# PCB_mini.net
KiCad netlist of a schematic drawn in Altium Designer
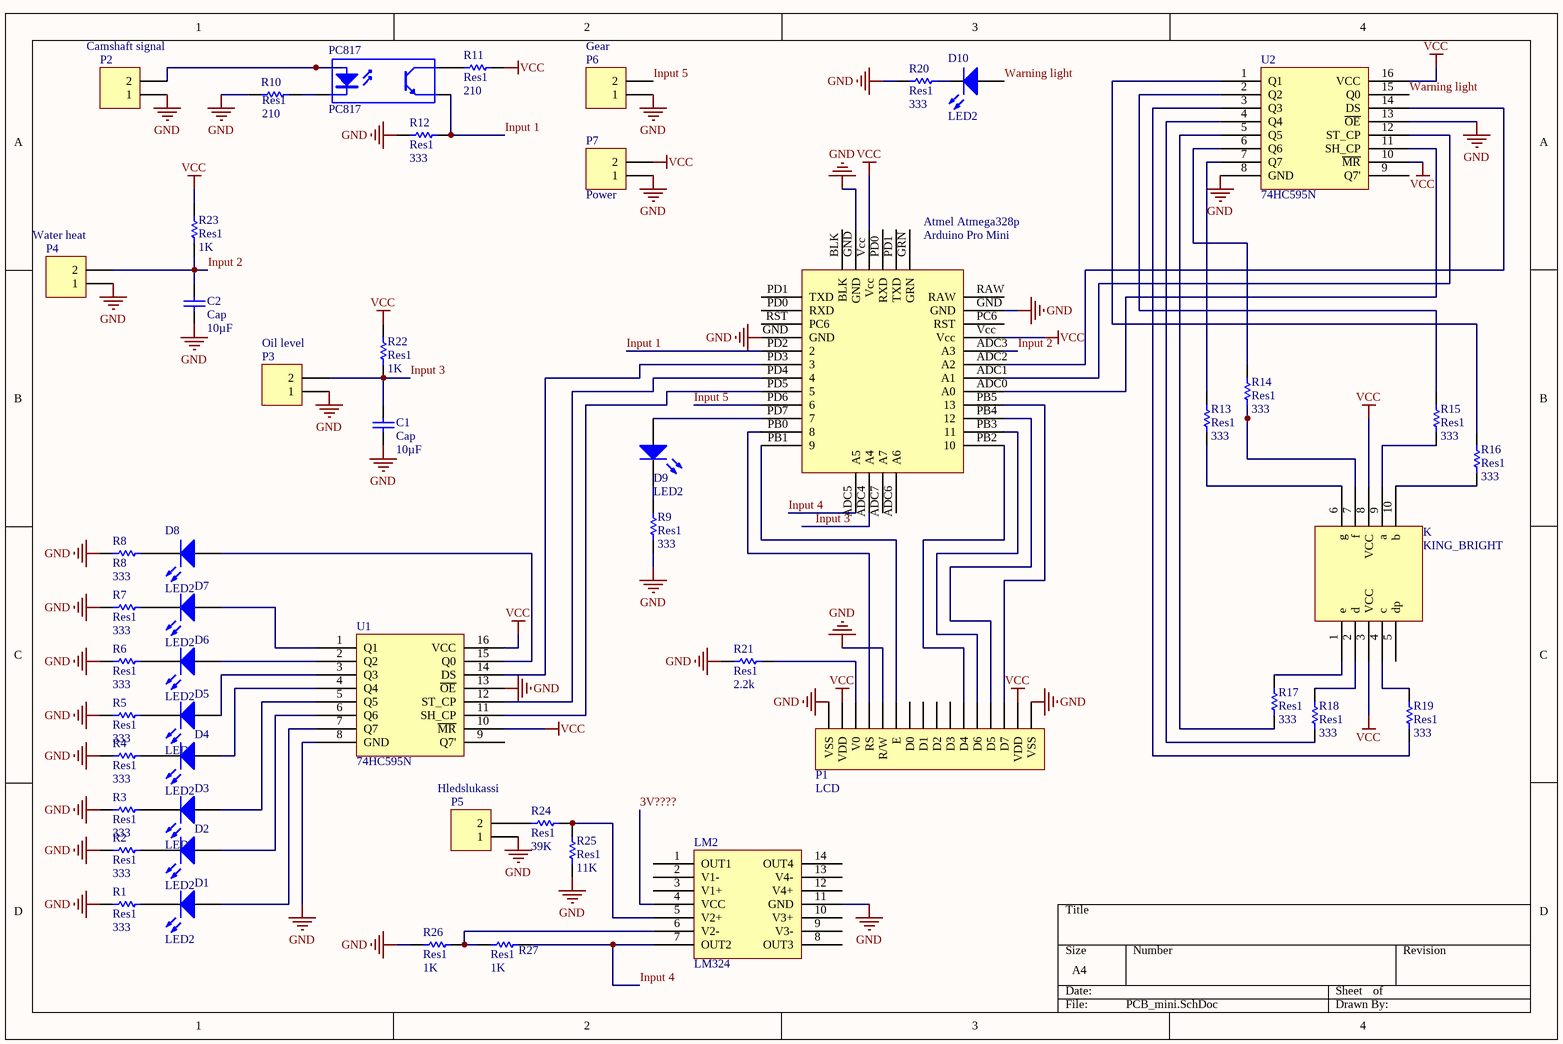
[diagram p0: PCB_mini.SchDoc]

(export (version "E")
  (design (tool "Eeschema 10.0.6"))
  (components
    (comp (ref "Arduino Pro Mini")
      (value "Atmel Atmega328p")
      (footprint "ArduinoProMini")
      (libsource (lib "ArduinoNano") (part "ArduinoProMini"))
    )
    (comp (ref "C1")
      (value "Cap")
      (footprint "1206 footprint")
      (fields (field (name "ALTIUM_VALUE") "10µF"))
      (libsource (lib "ArduinoNano (1)") (part "Cap"))
    )
    (comp (ref "C2")
      (value "Cap")
      (footprint "1206 footprint")
      (fields (field (name "ALTIUM_VALUE") "10µF"))
      (libsource (lib "ArduinoNano (1)") (part "Cap"))
    )
    (comp (ref "D1")
      (value "LED2")
      (footprint "3.2X1.6X1.1")
      (description "Typical RED, GREEN, YELLOW, AMBER GaAs LED")
      (fields (field (name "PUBLISHER") "Altium Limited"))
      (libsource (lib "Miscellaneous Devices") (part "LED2"))
    )
    (comp (ref "D2")
      (value "LED2")
      (footprint "3.2X1.6X1.1")
      (description "Typical RED, GREEN, YELLOW, AMBER GaAs LED")
      (fields (field (name "PUBLISHER") "Altium Limited"))
      (libsource (lib "Miscellaneous Devices") (part "LED2"))
    )
    (comp (ref "D3")
      (value "LED2")
      (footprint "3.2X1.6X1.1")
      (description "Typical RED, GREEN, YELLOW, AMBER GaAs LED")
      (fields (field (name "PUBLISHER") "Altium Limited"))
      (libsource (lib "Miscellaneous Devices") (part "LED2"))
    )
    (comp (ref "D4")
      (value "LED2")
      (footprint "3.2X1.6X1.1")
      (description "Typical RED, GREEN, YELLOW, AMBER GaAs LED")
      (fields (field (name "PUBLISHER") "Altium Limited"))
      (libsource (lib "Miscellaneous Devices") (part "LED2"))
    )
    (comp (ref "D5")
      (value "LED2")
      (footprint "3.2X1.6X1.1")
      (description "Typical RED, GREEN, YELLOW, AMBER GaAs LED")
      (fields (field (name "PUBLISHER") "Altium Limited"))
      (libsource (lib "Miscellaneous Devices") (part "LED2"))
    )
    (comp (ref "D6")
      (value "LED2")
      (footprint "3.2X1.6X1.1")
      (description "Typical RED, GREEN, YELLOW, AMBER GaAs LED")
      (fields (field (name "PUBLISHER") "Altium Limited"))
      (libsource (lib "Miscellaneous Devices") (part "LED2"))
    )
    (comp (ref "D7")
      (value "LED2")
      (footprint "3.2X1.6X1.1")
      (description "Typical RED, GREEN, YELLOW, AMBER GaAs LED")
      (fields (field (name "PUBLISHER") "Altium Limited"))
      (libsource (lib "Miscellaneous Devices") (part "LED2"))
    )
    (comp (ref "D8")
      (value "LED2")
      (footprint "3.2X1.6X1.1")
      (description "Typical RED, GREEN, YELLOW, AMBER GaAs LED")
      (fields (field (name "PUBLISHER") "Altium Limited"))
      (libsource (lib "Miscellaneous Devices") (part "LED2"))
    )
    (comp (ref "D9")
      (value "LED2")
      (footprint "3.2X1.6X1.1")
      (description "Typical RED, GREEN, YELLOW, AMBER GaAs LED")
      (fields (field (name "PUBLISHER") "Altium Limited"))
      (libsource (lib "Miscellaneous Devices") (part "LED2"))
    )
    (comp (ref "D10")
      (value "LED2")
      (footprint "3.2X1.6X1.1")
      (description "Typical RED, GREEN, YELLOW, AMBER GaAs LED")
      (fields (field (name "PUBLISHER") "Altium Limited"))
      (libsource (lib "Miscellaneous Devices") (part "LED2"))
    )
    (comp (ref "K")
      (value "KING_BRIGHT")
      (footprint "KNIGHT_BRIGHT")
      (libsource (lib "ArduinoNano") (part "KING_BRIGHT"))
    )
    (comp (ref "LM2") (value "LM324") (footprint "SOP-14") (libsource (lib "ArduinoNano") (part "LM324")))
    (comp (ref "P1")
      (value "LCD")
      (footprint "HDR1X16")
      (description "Header, 16-Pin")
      (fields (field (name "PUBLISHER") "Altium Limited"))
      (libsource (lib "Miscellaneous Connectors") (part "Header 16"))
    )
    (comp (ref "P2")
      (value "Camshaft signal")
      (footprint "HDR1X2")
      (description "Header, 2-Pin")
      (fields (field (name "PUBLISHER") "Altium Limited"))
      (libsource (lib "Miscellaneous Connectors") (part "Header 2"))
    )
    (comp (ref "P3")
      (value "Oil level")
      (footprint "HDR1X2")
      (description "Header, 2-Pin")
      (fields (field (name "PUBLISHER") "Altium Limited"))
      (libsource (lib "Miscellaneous Connectors") (part "Header 2"))
    )
    (comp (ref "P4")
      (value "Water heat")
      (footprint "HDR1X2")
      (description "Header, 2-Pin")
      (fields (field (name "PUBLISHER") "Altium Limited"))
      (libsource (lib "Miscellaneous Connectors") (part "Header 2"))
    )
    (comp (ref "P5")
      (value "Hledslukassi")
      (footprint "HDR1X2")
      (description "Header, 2-Pin")
      (fields (field (name "PUBLISHER") "Altium Limited"))
      (libsource (lib "Miscellaneous Connectors") (part "Header 2"))
    )
    (comp (ref "P6")
      (value "Gear")
      (footprint "HDR1X2")
      (description "Header, 2-Pin")
      (fields (field (name "PUBLISHER") "Altium Limited"))
      (libsource (lib "Miscellaneous Connectors") (part "Header 2"))
    )
    (comp (ref "P7")
      (value "Power")
      (footprint "HDR1X2")
      (description "Header, 2-Pin")
      (fields (field (name "PUBLISHER") "Altium Limited"))
      (libsource (lib "Miscellaneous Connectors") (part "Header 2"))
    )
    (comp (ref "PC817")
      (value "PC817")
      (footprint "PC817 SMT")
      (libsource (lib "ArduinoNano") (part "PC817"))
    )
    (comp (ref "R1")
      (value "Res1")
      (footprint "AXIAL-0.3")
      (description "Resistor")
      (fields (field (name "ALTIUM_VALUE") "333") (field (name "PUBLISHER") "Altium Limited"))
      (libsource (lib "Miscellaneous Devices") (part "Res1"))
    )
    (comp (ref "R2")
      (value "Res1")
      (footprint "AXIAL-0.3")
      (description "Resistor")
      (fields (field (name "ALTIUM_VALUE") "333") (field (name "PUBLISHER") "Altium Limited"))
      (libsource (lib "Miscellaneous Devices") (part "Res1"))
    )
    (comp (ref "R3")
      (value "Res1")
      (footprint "AXIAL-0.3")
      (description "Resistor")
      (fields (field (name "ALTIUM_VALUE") "333") (field (name "PUBLISHER") "Altium Limited"))
      (libsource (lib "Miscellaneous Devices") (part "Res1"))
    )
    (comp (ref "R4")
      (value "Res1")
      (footprint "AXIAL-0.3")
      (description "Resistor")
      (fields (field (name "ALTIUM_VALUE") "333") (field (name "PUBLISHER") "Altium Limited"))
      (libsource (lib "Miscellaneous Devices") (part "Res1"))
    )
    (comp (ref "R5")
      (value "Res1")
      (footprint "AXIAL-0.3")
      (description "Resistor")
      (fields (field (name "ALTIUM_VALUE") "333") (field (name "PUBLISHER") "Altium Limited"))
      (libsource (lib "Miscellaneous Devices") (part "Res1"))
    )
    (comp (ref "R6")
      (value "Res1")
      (footprint "AXIAL-0.3")
      (description "Resistor")
      (fields (field (name "ALTIUM_VALUE") "333") (field (name "PUBLISHER") "Altium Limited"))
      (libsource (lib "Miscellaneous Devices") (part "Res1"))
    )
    (comp (ref "R7")
      (value "Res1")
      (footprint "AXIAL-0.3")
      (description "Resistor")
      (fields (field (name "ALTIUM_VALUE") "333") (field (name "PUBLISHER") "Altium Limited"))
      (libsource (lib "Miscellaneous Devices") (part "Res1"))
    )
    (comp (ref "R8")
      (value "R8")
      (footprint "AXIAL-0.3")
      (description "Resistor")
      (fields (field (name "ALTIUM_VALUE") "333") (field (name "PUBLISHER") "Altium Limited"))
      (libsource (lib "Miscellaneous Devices") (part "Res1"))
    )
    (comp (ref "R9")
      (value "Res1")
      (footprint "AXIAL-0.3")
      (description "Resistor")
      (fields (field (name "ALTIUM_VALUE") "333") (field (name "PUBLISHER") "Altium Limited"))
      (libsource (lib "Miscellaneous Devices") (part "Res1"))
    )
    (comp (ref "R10")
      (value "Res1")
      (footprint "AXIAL-0.3")
      (description "Resistor")
      (fields (field (name "ALTIUM_VALUE") "210") (field (name "PUBLISHER") "Altium Limited"))
      (libsource (lib "Miscellaneous Devices") (part "Res1"))
    )
    (comp (ref "R11")
      (value "Res1")
      (footprint "AXIAL-0.3")
      (description "Resistor")
      (fields (field (name "ALTIUM_VALUE") "210") (field (name "PUBLISHER") "Altium Limited"))
      (libsource (lib "Miscellaneous Devices") (part "Res1"))
    )
    (comp (ref "R12")
      (value "Res1")
      (footprint "AXIAL-0.3")
      (description "Resistor")
      (fields (field (name "ALTIUM_VALUE") "333") (field (name "PUBLISHER") "Altium Limited"))
      (libsource (lib "Miscellaneous Devices") (part "Res1"))
    )
    (comp (ref "R13")
      (value "Res1")
      (footprint "AXIAL-0.3")
      (description "Resistor")
      (fields (field (name "ALTIUM_VALUE") "333") (field (name "PUBLISHER") "Altium Limited"))
      (libsource (lib "Miscellaneous Devices") (part "Res1"))
    )
    (comp (ref "R14")
      (value "Res1")
      (footprint "AXIAL-0.3")
      (description "Resistor")
      (fields (field (name "ALTIUM_VALUE") "333") (field (name "PUBLISHER") "Altium Limited"))
      (libsource (lib "Miscellaneous Devices") (part "Res1"))
    )
    (comp (ref "R15")
      (value "Res1")
      (footprint "AXIAL-0.3")
      (description "Resistor")
      (fields (field (name "ALTIUM_VALUE") "333") (field (name "PUBLISHER") "Altium Limited"))
      (libsource (lib "Miscellaneous Devices") (part "Res1"))
    )
    (comp (ref "R16")
      (value "Res1")
      (footprint "AXIAL-0.3")
      (description "Resistor")
      (fields (field (name "ALTIUM_VALUE") "333") (field (name "PUBLISHER") "Altium Limited"))
      (libsource (lib "Miscellaneous Devices") (part "Res1"))
    )
    (comp (ref "R17")
      (value "Res1")
      (footprint "AXIAL-0.3")
      (description "Resistor")
      (fields (field (name "ALTIUM_VALUE") "333") (field (name "PUBLISHER") "Altium Limited"))
      (libsource (lib "Miscellaneous Devices") (part "Res1"))
    )
    (comp (ref "R18")
      (value "Res1")
      (footprint "AXIAL-0.3")
      (description "Resistor")
      (fields (field (name "ALTIUM_VALUE") "333") (field (name "PUBLISHER") "Altium Limited"))
      (libsource (lib "Miscellaneous Devices") (part "Res1"))
    )
    (comp (ref "R19")
      (value "Res1")
      (footprint "AXIAL-0.3")
      (description "Resistor")
      (fields (field (name "ALTIUM_VALUE") "333") (field (name "PUBLISHER") "Altium Limited"))
      (libsource (lib "Miscellaneous Devices") (part "Res1"))
    )
    (comp (ref "R20")
      (value "Res1")
      (footprint "AXIAL-0.3")
      (description "Resistor")
      (fields (field (name "ALTIUM_VALUE") "333") (field (name "PUBLISHER") "Altium Limited"))
      (libsource (lib "Miscellaneous Devices") (part "Res1"))
    )
    (comp (ref "R21")
      (value "Res1")
      (footprint "AXIAL-0.3")
      (description "Resistor")
      (fields (field (name "ALTIUM_VALUE") "2.2k") (field (name "PUBLISHER") "Altium Limited"))
      (libsource (lib "Miscellaneous Devices") (part "Res1"))
    )
    (comp (ref "R22")
      (value "Res1")
      (footprint "AXIAL-0.3")
      (description "Resistor")
      (fields (field (name "ALTIUM_VALUE") "1K") (field (name "PUBLISHER") "Altium Limited"))
      (libsource (lib "Miscellaneous Devices") (part "Res1"))
    )
    (comp (ref "R23")
      (value "Res1")
      (footprint "AXIAL-0.3")
      (description "Resistor")
      (fields (field (name "ALTIUM_VALUE") "1K") (field (name "PUBLISHER") "Altium Limited"))
      (libsource (lib "Miscellaneous Devices") (part "Res1"))
    )
    (comp (ref "R24")
      (value "Res1")
      (footprint "AXIAL-0.3")
      (description "Resistor")
      (fields (field (name "ALTIUM_VALUE") "39K") (field (name "PUBLISHER") "Altium Limited"))
      (libsource (lib "Miscellaneous Devices") (part "Res1"))
    )
    (comp (ref "R25")
      (value "Res1")
      (footprint "AXIAL-0.3")
      (description "Resistor")
      (fields (field (name "ALTIUM_VALUE") "11K") (field (name "PUBLISHER") "Altium Limited"))
      (libsource (lib "Miscellaneous Devices") (part "Res1"))
    )
    (comp (ref "R26")
      (value "Res1")
      (footprint "AXIAL-0.3")
      (description "Resistor")
      (fields (field (name "ALTIUM_VALUE") "1K") (field (name "PUBLISHER") "Altium Limited"))
      (libsource (lib "Miscellaneous Devices") (part "Res1"))
    )
    (comp (ref "R27")
      (value "Res1")
      (footprint "AXIAL-0.3")
      (description "Resistor")
      (fields (field (name "ALTIUM_VALUE") "1K") (field (name "PUBLISHER") "Altium Limited"))
      (libsource (lib "Miscellaneous Devices") (part "Res1"))
    )
    (comp (ref "U1") (value "74HC595N") (footprint "N14A") (libsource (lib "ArduinoNano") (part "SN74LS06N")))
    (comp (ref "U2") (value "74HC595N") (footprint "N14A") (libsource (lib "ArduinoNano") (part "SN74LS06N")))
  )
  (nets
    (net (code "1") (name "/3V????") (class "Default")
      (node (ref "LM2") (pin "4") (pinfunction "VCC_4") (pintype "passive"))
    )
    (net (code "2") (name "/Input 1") (class "Default")
      (node (ref "Arduino Pro Mini") (pin "PD2") (pinfunction "2_PD2") (pintype "passive"))
      (node (ref "PC817") (pin "3") (pinfunction "E_3") (pintype "passive"))
      (node (ref "R12") (pin "1") (pinfunction "1_1") (pintype "passive"))
    )
    (net (code "3") (name "/Input 2") (class "Default")
      (node (ref "Arduino Pro Mini") (pin "ADC3") (pinfunction "A3_ADC3") (pintype "passive"))
      (node (ref "C2") (pin "2") (pinfunction "2_2") (pintype "passive"))
      (node (ref "P4") (pin "2") (pinfunction "2_2") (pintype "passive"))
      (node (ref "R23") (pin "2") (pinfunction "2_2") (pintype "passive"))
    )
    (net (code "4") (name "/Input 3") (class "Default")
      (node (ref "Arduino Pro Mini") (pin "ADC4") (pinfunction "A4_ADC4") (pintype "passive"))
      (node (ref "C1") (pin "2") (pinfunction "2_2") (pintype "passive"))
      (node (ref "P3") (pin "2") (pinfunction "2_2") (pintype "passive"))
      (node (ref "R22") (pin "2") (pinfunction "2_2") (pintype "passive"))
    )
    (net (code "5") (name "/Input 4") (class "Default")
      (node (ref "Arduino Pro Mini") (pin "ADC5") (pinfunction "A5_ADC5") (pintype "passive"))
      (node (ref "LM2") (pin "7") (pinfunction "OUT2_7") (pintype "passive"))
      (node (ref "R27") (pin "2") (pinfunction "2_2") (pintype "passive"))
    )
    (net (code "6") (name "/Input 5") (class "Default")
      (node (ref "Arduino Pro Mini") (pin "PD6") (pinfunction "6_PD6") (pintype "passive"))
      (node (ref "P6") (pin "2") (pinfunction "2_2") (pintype "passive"))
    )
    (net (code "7") (name "/Warning light") (class "Default")
      (node (ref "D10") (pin "1") (pinfunction "A_1") (pintype "passive"))
      (node (ref "U2") (pin "15") (pinfunction "Q0_15") (pintype "passive"))
    )
    (net (code "8") (name "GND") (class "Default")
      (node (ref "Arduino Pro Mini") (pin "GND") (pinfunction "GND_GND") (pintype "passive"))
      (node (ref "C1") (pin "1") (pinfunction "1_1") (pintype "passive"))
      (node (ref "C2") (pin "1") (pinfunction "1_1") (pintype "passive"))
      (node (ref "LM2") (pin "11") (pinfunction "GND_11") (pintype "passive"))
      (node (ref "P1") (pin "1") (pinfunction "VSS_1") (pintype "passive"))
      (node (ref "P1") (pin "16") (pinfunction "VSS_16") (pintype "passive"))
      (node (ref "P1") (pin "5") (pinfunction "R/W_5") (pintype "passive"))
      (node (ref "P2") (pin "1") (pinfunction "1_1") (pintype "passive"))
      (node (ref "P3") (pin "1") (pinfunction "1_1") (pintype "passive"))
      (node (ref "P4") (pin "1") (pinfunction "1_1") (pintype "passive"))
      (node (ref "P5") (pin "1") (pinfunction "1_1") (pintype "passive"))
      (node (ref "P6") (pin "1") (pinfunction "1_1") (pintype "passive"))
      (node (ref "P7") (pin "1") (pinfunction "1_1") (pintype "passive"))
      (node (ref "R1") (pin "2") (pinfunction "2_2") (pintype "passive"))
      (node (ref "R10") (pin "1") (pinfunction "1_1") (pintype "passive"))
      (node (ref "R12") (pin "2") (pinfunction "2_2") (pintype "passive"))
      (node (ref "R2") (pin "2") (pinfunction "2_2") (pintype "passive"))
      (node (ref "R20") (pin "2") (pinfunction "2_2") (pintype "passive"))
      (node (ref "R21") (pin "1") (pinfunction "1_1") (pintype "passive"))
      (node (ref "R25") (pin "2") (pinfunction "2_2") (pintype "passive"))
      (node (ref "R26") (pin "2") (pinfunction "2_2") (pintype "passive"))
      (node (ref "R3") (pin "2") (pinfunction "2_2") (pintype "passive"))
      (node (ref "R4") (pin "2") (pinfunction "2_2") (pintype "passive"))
      (node (ref "R5") (pin "2") (pinfunction "2_2") (pintype "passive"))
      (node (ref "R6") (pin "2") (pinfunction "2_2") (pintype "passive"))
      (node (ref "R7") (pin "2") (pinfunction "2_2") (pintype "passive"))
      (node (ref "R8") (pin "2") (pinfunction "2_2") (pintype "passive"))
      (node (ref "R9") (pin "2") (pinfunction "2_2") (pintype "passive"))
      (node (ref "U1") (pin "13") (pinfunction "~{OE}_13") (pintype "passive"))
      (node (ref "U1") (pin "8") (pinfunction "GND_8") (pintype "passive"))
      (node (ref "U2") (pin "13") (pinfunction "~{OE}_13") (pintype "passive"))
      (node (ref "U2") (pin "8") (pinfunction "GND_8") (pintype "passive"))
    )
    (net (code "9") (name "Net-(Arduino Pro Mini-3)") (class "Default")
      (node (ref "Arduino Pro Mini") (pin "PD3") (pinfunction "3_PD3") (pintype "passive"))
      (node (ref "U1") (pin "14") (pinfunction "DS_14") (pintype "passive"))
    )
    (net (code "10") (name "Net-(Arduino Pro Mini-4)") (class "Default")
      (node (ref "Arduino Pro Mini") (pin "PD4") (pinfunction "4_PD4") (pintype "passive"))
      (node (ref "U1") (pin "12") (pinfunction "ST_CP_12") (pintype "passive"))
    )
    (net (code "11") (name "Net-(Arduino Pro Mini-5)") (class "Default")
      (node (ref "Arduino Pro Mini") (pin "PD5") (pinfunction "5_PD5") (pintype "passive"))
      (node (ref "U1") (pin "11") (pinfunction "SH_CP_11") (pintype "passive"))
    )
    (net (code "12") (name "Net-(Arduino Pro Mini-7)") (class "Default")
      (node (ref "Arduino Pro Mini") (pin "PD7") (pinfunction "7_PD7") (pintype "passive"))
      (node (ref "D9") (pin "1") (pinfunction "A_1") (pintype "passive"))
    )
    (net (code "13") (name "Net-(Arduino Pro Mini-8)") (class "Default")
      (node (ref "Arduino Pro Mini") (pin "PB0") (pinfunction "8_PB0") (pintype "passive"))
      (node (ref "P1") (pin "4") (pinfunction "RS_4") (pintype "passive"))
    )
    (net (code "14") (name "Net-(Arduino Pro Mini-9)") (class "Default")
      (node (ref "Arduino Pro Mini") (pin "PB1") (pinfunction "9_PB1") (pintype "passive"))
      (node (ref "P1") (pin "6") (pinfunction "E_6") (pintype "passive"))
    )
    (net (code "15") (name "Net-(Arduino Pro Mini-10)") (class "Default")
      (node (ref "Arduino Pro Mini") (pin "PB2") (pinfunction "10_PB2") (pintype "passive"))
      (node (ref "P1") (pin "11") (pinfunction "D4_11") (pintype "passive"))
    )
    (net (code "16") (name "Net-(Arduino Pro Mini-11)") (class "Default")
      (node (ref "Arduino Pro Mini") (pin "PB3") (pinfunction "11_PB3") (pintype "passive"))
      (node (ref "P1") (pin "13") (pinfunction "D6_13") (pintype "passive"))
    )
    (net (code "17") (name "Net-(Arduino Pro Mini-12)") (class "Default")
      (node (ref "Arduino Pro Mini") (pin "PB4") (pinfunction "12_PB4") (pintype "passive"))
      (node (ref "P1") (pin "12") (pinfunction "D5_12") (pintype "passive"))
    )
    (net (code "18") (name "Net-(Arduino Pro Mini-13)") (class "Default")
      (node (ref "Arduino Pro Mini") (pin "PB5") (pinfunction "13_PB5") (pintype "passive"))
      (node (ref "P1") (pin "14") (pinfunction "D7_14") (pintype "passive"))
    )
    (net (code "19") (name "Net-(Arduino Pro Mini-A0)") (class "Default")
      (node (ref "Arduino Pro Mini") (pin "ADC0") (pinfunction "A0_ADC0") (pintype "passive"))
      (node (ref "U2") (pin "11") (pinfunction "SH_CP_11") (pintype "passive"))
    )
    (net (code "20") (name "Net-(Arduino Pro Mini-A1)") (class "Default")
      (node (ref "Arduino Pro Mini") (pin "ADC1") (pinfunction "A1_ADC1") (pintype "passive"))
      (node (ref "U2") (pin "12") (pinfunction "ST_CP_12") (pintype "passive"))
    )
    (net (code "21") (name "Net-(Arduino Pro Mini-A2)") (class "Default")
      (node (ref "Arduino Pro Mini") (pin "ADC2") (pinfunction "A2_ADC2") (pintype "passive"))
      (node (ref "U2") (pin "14") (pinfunction "DS_14") (pintype "passive"))
    )
    (net (code "22") (name "Net-(D1-A)") (class "Default")
      (node (ref "D1") (pin "1") (pinfunction "A_1") (pintype "passive"))
      (node (ref "U1") (pin "7") (pinfunction "Q7_7") (pintype "passive"))
    )
    (net (code "23") (name "Net-(D1-K)") (class "Default")
      (node (ref "D1") (pin "2") (pinfunction "K_2") (pintype "passive"))
      (node (ref "R1") (pin "1") (pinfunction "1_1") (pintype "passive"))
    )
    (net (code "24") (name "Net-(D2-A)") (class "Default")
      (node (ref "D2") (pin "1") (pinfunction "A_1") (pintype "passive"))
      (node (ref "U1") (pin "6") (pinfunction "Q6_6") (pintype "passive"))
    )
    (net (code "25") (name "Net-(D2-K)") (class "Default")
      (node (ref "D2") (pin "2") (pinfunction "K_2") (pintype "passive"))
      (node (ref "R2") (pin "1") (pinfunction "1_1") (pintype "passive"))
    )
    (net (code "26") (name "Net-(D3-A)") (class "Default")
      (node (ref "D3") (pin "1") (pinfunction "A_1") (pintype "passive"))
      (node (ref "U1") (pin "5") (pinfunction "Q5_5") (pintype "passive"))
    )
    (net (code "27") (name "Net-(D3-K)") (class "Default")
      (node (ref "D3") (pin "2") (pinfunction "K_2") (pintype "passive"))
      (node (ref "R3") (pin "1") (pinfunction "1_1") (pintype "passive"))
    )
    (net (code "28") (name "Net-(D4-A)") (class "Default")
      (node (ref "D4") (pin "1") (pinfunction "A_1") (pintype "passive"))
      (node (ref "U1") (pin "4") (pinfunction "Q4_4") (pintype "passive"))
    )
    (net (code "29") (name "Net-(D4-K)") (class "Default")
      (node (ref "D4") (pin "2") (pinfunction "K_2") (pintype "passive"))
      (node (ref "R4") (pin "1") (pinfunction "1_1") (pintype "passive"))
    )
    (net (code "30") (name "Net-(D5-A)") (class "Default")
      (node (ref "D5") (pin "1") (pinfunction "A_1") (pintype "passive"))
      (node (ref "U1") (pin "3") (pinfunction "Q3_3") (pintype "passive"))
    )
    (net (code "31") (name "Net-(D5-K)") (class "Default")
      (node (ref "D5") (pin "2") (pinfunction "K_2") (pintype "passive"))
      (node (ref "R5") (pin "1") (pinfunction "1_1") (pintype "passive"))
    )
    (net (code "32") (name "Net-(D6-A)") (class "Default")
      (node (ref "D6") (pin "1") (pinfunction "A_1") (pintype "passive"))
      (node (ref "U1") (pin "2") (pinfunction "Q2_2") (pintype "passive"))
    )
    (net (code "33") (name "Net-(D6-K)") (class "Default")
      (node (ref "D6") (pin "2") (pinfunction "K_2") (pintype "passive"))
      (node (ref "R6") (pin "1") (pinfunction "1_1") (pintype "passive"))
    )
    (net (code "34") (name "Net-(D7-A)") (class "Default")
      (node (ref "D7") (pin "1") (pinfunction "A_1") (pintype "passive"))
      (node (ref "U1") (pin "1") (pinfunction "Q1_1") (pintype "passive"))
    )
    (net (code "35") (name "Net-(D7-K)") (class "Default")
      (node (ref "D7") (pin "2") (pinfunction "K_2") (pintype "passive"))
      (node (ref "R7") (pin "1") (pinfunction "1_1") (pintype "passive"))
    )
    (net (code "36") (name "Net-(D8-A)") (class "Default")
      (node (ref "D8") (pin "1") (pinfunction "A_1") (pintype "passive"))
      (node (ref "U1") (pin "15") (pinfunction "Q0_15") (pintype "passive"))
    )
    (net (code "37") (name "Net-(D8-K)") (class "Default")
      (node (ref "D8") (pin "2") (pinfunction "K_2") (pintype "passive"))
      (node (ref "R8") (pin "1") (pinfunction "1_1") (pintype "passive"))
    )
    (net (code "38") (name "Net-(D9-K)") (class "Default")
      (node (ref "D9") (pin "2") (pinfunction "K_2") (pintype "passive"))
      (node (ref "R9") (pin "1") (pinfunction "1_1") (pintype "passive"))
    )
    (net (code "39") (name "Net-(D10-K)") (class "Default")
      (node (ref "D10") (pin "2") (pinfunction "K_2") (pintype "passive"))
      (node (ref "R20") (pin "1") (pinfunction "1_1") (pintype "passive"))
    )
    (net (code "40") (name "Net-(K-a)") (class "Default")
      (node (ref "K") (pin "9") (pinfunction "a_9") (pintype "passive"))
      (node (ref "R15") (pin "2") (pinfunction "2_2") (pintype "passive"))
    )
    (net (code "41") (name "Net-(K-b)") (class "Default")
      (node (ref "K") (pin "10") (pinfunction "b_10") (pintype "passive"))
      (node (ref "R16") (pin "2") (pinfunction "2_2") (pintype "passive"))
    )
    (net (code "42") (name "Net-(K-c)") (class "Default")
      (node (ref "K") (pin "4") (pinfunction "c_4") (pintype "passive"))
      (node (ref "R19") (pin "1") (pinfunction "1_1") (pintype "passive"))
    )
    (net (code "43") (name "Net-(K-d)") (class "Default")
      (node (ref "K") (pin "2") (pinfunction "d_2") (pintype "passive"))
      (node (ref "R18") (pin "1") (pinfunction "1_1") (pintype "passive"))
    )
    (net (code "44") (name "Net-(K-e)") (class "Default")
      (node (ref "K") (pin "1") (pinfunction "e_1") (pintype "passive"))
      (node (ref "R17") (pin "1") (pinfunction "1_1") (pintype "passive"))
    )
    (net (code "45") (name "Net-(K-f)") (class "Default")
      (node (ref "K") (pin "7") (pinfunction "f_7") (pintype "passive"))
      (node (ref "R14") (pin "1") (pinfunction "1_1") (pintype "passive"))
    )
    (net (code "46") (name "Net-(K-g)") (class "Default")
      (node (ref "K") (pin "6") (pinfunction "g_6") (pintype "passive"))
      (node (ref "R13") (pin "2") (pinfunction "2_2") (pintype "passive"))
    )
    (net (code "47") (name "Net-(LM2-V2+)") (class "Default")
      (node (ref "LM2") (pin "5") (pinfunction "V2+_5") (pintype "passive"))
      (node (ref "R24") (pin "2") (pinfunction "2_2") (pintype "passive"))
      (node (ref "R25") (pin "1") (pinfunction "1_1") (pintype "passive"))
    )
    (net (code "48") (name "Net-(LM2-V2-)") (class "Default")
      (node (ref "LM2") (pin "6") (pinfunction "V2-_6") (pintype "passive"))
      (node (ref "R26") (pin "1") (pinfunction "1_1") (pintype "passive"))
      (node (ref "R27") (pin "1") (pinfunction "1_1") (pintype "passive"))
    )
    (net (code "49") (name "Net-(P1-V0)") (class "Default")
      (node (ref "P1") (pin "3") (pinfunction "V0_3") (pintype "passive"))
      (node (ref "R21") (pin "2") (pinfunction "2_2") (pintype "passive"))
    )
    (net (code "50") (name "Net-(P5-Pad2)") (class "Default")
      (node (ref "P5") (pin "2") (pinfunction "2_2") (pintype "passive"))
      (node (ref "R24") (pin "1") (pinfunction "1_1") (pintype "passive"))
    )
    (net (code "51") (name "Net-(PC817-A)") (class "Default")
      (node (ref "P2") (pin "2") (pinfunction "2_2") (pintype "passive"))
      (node (ref "PC817") (pin "1") (pinfunction "A_1") (pintype "passive"))
    )
    (net (code "52") (name "Net-(PC817-C)") (class "Default")
      (node (ref "PC817") (pin "4") (pinfunction "C_4") (pintype "passive"))
      (node (ref "R11") (pin "2") (pinfunction "2_2") (pintype "passive"))
    )
    (net (code "53") (name "Net-(PC817-K)") (class "Default")
      (node (ref "PC817") (pin "2") (pinfunction "K_2") (pintype "passive"))
      (node (ref "R10") (pin "2") (pinfunction "2_2") (pintype "passive"))
    )
    (net (code "54") (name "Net-(U2-Q1)") (class "Default")
      (node (ref "R16") (pin "1") (pinfunction "1_1") (pintype "passive"))
      (node (ref "U2") (pin "1") (pinfunction "Q1_1") (pintype "passive"))
    )
    (net (code "55") (name "Net-(U2-Q2)") (class "Default")
      (node (ref "R15") (pin "1") (pinfunction "1_1") (pintype "passive"))
      (node (ref "U2") (pin "2") (pinfunction "Q2_2") (pintype "passive"))
    )
    (net (code "56") (name "Net-(U2-Q3)") (class "Default")
      (node (ref "R19") (pin "2") (pinfunction "2_2") (pintype "passive"))
      (node (ref "U2") (pin "3") (pinfunction "Q3_3") (pintype "passive"))
    )
    (net (code "57") (name "Net-(U2-Q4)") (class "Default")
      (node (ref "R18") (pin "2") (pinfunction "2_2") (pintype "passive"))
      (node (ref "U2") (pin "4") (pinfunction "Q4_4") (pintype "passive"))
    )
    (net (code "58") (name "Net-(U2-Q5)") (class "Default")
      (node (ref "R17") (pin "2") (pinfunction "2_2") (pintype "passive"))
      (node (ref "U2") (pin "5") (pinfunction "Q5_5") (pintype "passive"))
    )
    (net (code "59") (name "Net-(U2-Q6)") (class "Default")
      (node (ref "R14") (pin "2") (pinfunction "2_2") (pintype "passive"))
      (node (ref "U2") (pin "6") (pinfunction "Q6_6") (pintype "passive"))
    )
    (net (code "60") (name "Net-(U2-Q7)") (class "Default")
      (node (ref "R13") (pin "1") (pinfunction "1_1") (pintype "passive"))
      (node (ref "U2") (pin "7") (pinfunction "Q7_7") (pintype "passive"))
    )
    (net (code "61") (name "VCC") (class "Default")
      (node (ref "Arduino Pro Mini") (pin "Vcc") (pinfunction "Vcc_Vcc") (pintype "passive"))
      (node (ref "K") (pin "3") (pinfunction "VCC_3") (pintype "passive"))
      (node (ref "K") (pin "8") (pinfunction "VCC_8") (pintype "passive"))
      (node (ref "P1") (pin "15") (pinfunction "VDD_15") (pintype "passive"))
      (node (ref "P1") (pin "2") (pinfunction "VDD_2") (pintype "passive"))
      (node (ref "P7") (pin "2") (pinfunction "2_2") (pintype "passive"))
      (node (ref "R11") (pin "1") (pinfunction "1_1") (pintype "passive"))
      (node (ref "R22") (pin "1") (pinfunction "1_1") (pintype "passive"))
      (node (ref "R23") (pin "1") (pinfunction "1_1") (pintype "passive"))
      (node (ref "U1") (pin "10") (pinfunction "~{MR}_10") (pintype "passive"))
      (node (ref "U1") (pin "16") (pinfunction "VCC_16") (pintype "passive"))
      (node (ref "U2") (pin "10") (pinfunction "~{MR}_10") (pintype "passive"))
      (node (ref "U2") (pin "16") (pinfunction "VCC_16") (pintype "passive"))
    )
    (net (code "62") (name "unconnected-(Arduino Pro Mini-A6-PadADC6)") (class "Default")
      (node (ref "Arduino Pro Mini") (pin "ADC6") (pinfunction "A6_ADC6") (pintype "passive"))
    )
    (net (code "63") (name "unconnected-(Arduino Pro Mini-A7-PadADC7)") (class "Default")
      (node (ref "Arduino Pro Mini") (pin "ADC7") (pinfunction "A7_ADC7") (pintype "passive"))
    )
    (net (code "64") (name "unconnected-(Arduino Pro Mini-PC6-PadRST)") (class "Default")
      (node (ref "Arduino Pro Mini") (pin "RST") (pinfunction "PC6_RST") (pintype "passive"))
    )
    (net (code "65") (name "unconnected-(Arduino Pro Mini-PadBLK)") (class "Default")
      (node (ref "Arduino Pro Mini") (pin "BLK") (pinfunction "BLK_BLK") (pintype "passive"))
    )
    (net (code "66") (name "unconnected-(Arduino Pro Mini-PadGRN)") (class "Default")
      (node (ref "Arduino Pro Mini") (pin "GRN") (pinfunction "GRN_GRN") (pintype "passive"))
    )
    (net (code "67") (name "unconnected-(Arduino Pro Mini-PadRAW)") (class "Default")
      (node (ref "Arduino Pro Mini") (pin "RAW") (pinfunction "RAW_RAW") (pintype "passive"))
    )
    (net (code "68") (name "unconnected-(Arduino Pro Mini-RST-PadPC6)") (class "Default")
      (node (ref "Arduino Pro Mini") (pin "PC6") (pinfunction "RST_PC6") (pintype "passive"))
    )
    (net (code "69") (name "unconnected-(Arduino Pro Mini-RXD-PadPD0)") (class "Default")
      (node (ref "Arduino Pro Mini") (pin "PD0") (pinfunction "RXD_PD0") (pintype "passive"))
    )
    (net (code "70") (name "unconnected-(Arduino Pro Mini-RXD-PadPD0)_1") (class "Default")
      (node (ref "Arduino Pro Mini") (pin "PD0") (pinfunction "RXD_PD0") (pintype "passive"))
    )
    (net (code "71") (name "unconnected-(Arduino Pro Mini-TXD-PadPD1)") (class "Default")
      (node (ref "Arduino Pro Mini") (pin "PD1") (pinfunction "TXD_PD1") (pintype "passive"))
    )
    (net (code "72") (name "unconnected-(Arduino Pro Mini-TXD-PadPD1)_1") (class "Default")
      (node (ref "Arduino Pro Mini") (pin "PD1") (pinfunction "TXD_PD1") (pintype "passive"))
    )
    (net (code "73") (name "unconnected-(K-dp-Pad5)") (class "Default")
      (node (ref "K") (pin "5") (pinfunction "dp_5") (pintype "passive"))
    )
    (net (code "74") (name "unconnected-(LM2-OUT1-Pad1)") (class "Default")
      (node (ref "LM2") (pin "1") (pinfunction "OUT1_1") (pintype "passive"))
    )
    (net (code "75") (name "unconnected-(LM2-OUT3-Pad8)") (class "Default")
      (node (ref "LM2") (pin "8") (pinfunction "OUT3_8") (pintype "passive"))
    )
    (net (code "76") (name "unconnected-(LM2-OUT4-Pad14)") (class "Default")
      (node (ref "LM2") (pin "14") (pinfunction "OUT4_14") (pintype "passive"))
    )
    (net (code "77") (name "unconnected-(LM2-V1+-Pad3)") (class "Default")
      (node (ref "LM2") (pin "3") (pinfunction "V1+_3") (pintype "passive"))
    )
    (net (code "78") (name "unconnected-(LM2-V1--Pad2)") (class "Default")
      (node (ref "LM2") (pin "2") (pinfunction "V1-_2") (pintype "passive"))
    )
    (net (code "79") (name "unconnected-(LM2-V3+-Pad10)") (class "Default")
      (node (ref "LM2") (pin "10") (pinfunction "V3+_10") (pintype "passive"))
    )
    (net (code "80") (name "unconnected-(LM2-V3--Pad9)") (class "Default")
      (node (ref "LM2") (pin "9") (pinfunction "V3-_9") (pintype "passive"))
    )
    (net (code "81") (name "unconnected-(LM2-V4+-Pad12)") (class "Default")
      (node (ref "LM2") (pin "12") (pinfunction "V4+_12") (pintype "passive"))
    )
    (net (code "82") (name "unconnected-(LM2-V4--Pad13)") (class "Default")
      (node (ref "LM2") (pin "13") (pinfunction "V4-_13") (pintype "passive"))
    )
    (net (code "83") (name "unconnected-(P1-D0-Pad7)") (class "Default")
      (node (ref "P1") (pin "7") (pinfunction "D0_7") (pintype "passive"))
    )
    (net (code "84") (name "unconnected-(P1-D1-Pad8)") (class "Default")
      (node (ref "P1") (pin "8") (pinfunction "D1_8") (pintype "passive"))
    )
    (net (code "85") (name "unconnected-(P1-D2-Pad9)") (class "Default")
      (node (ref "P1") (pin "9") (pinfunction "D2_9") (pintype "passive"))
    )
    (net (code "86") (name "unconnected-(P1-D3-Pad10)") (class "Default")
      (node (ref "P1") (pin "10") (pinfunction "D3_10") (pintype "passive"))
    )
    (net (code "87") (name "unconnected-(U1-Q7'-Pad9)") (class "Default")
      (node (ref "U1") (pin "9") (pinfunction "Q7'_9") (pintype "passive"))
    )
    (net (code "88") (name "unconnected-(U2-Q7'-Pad9)") (class "Default")
      (node (ref "U2") (pin "9") (pinfunction "Q7'_9") (pintype "passive"))
    )
  )
)
